# Sheet1.net
KiCad netlist of a schematic drawn in Altium Designer
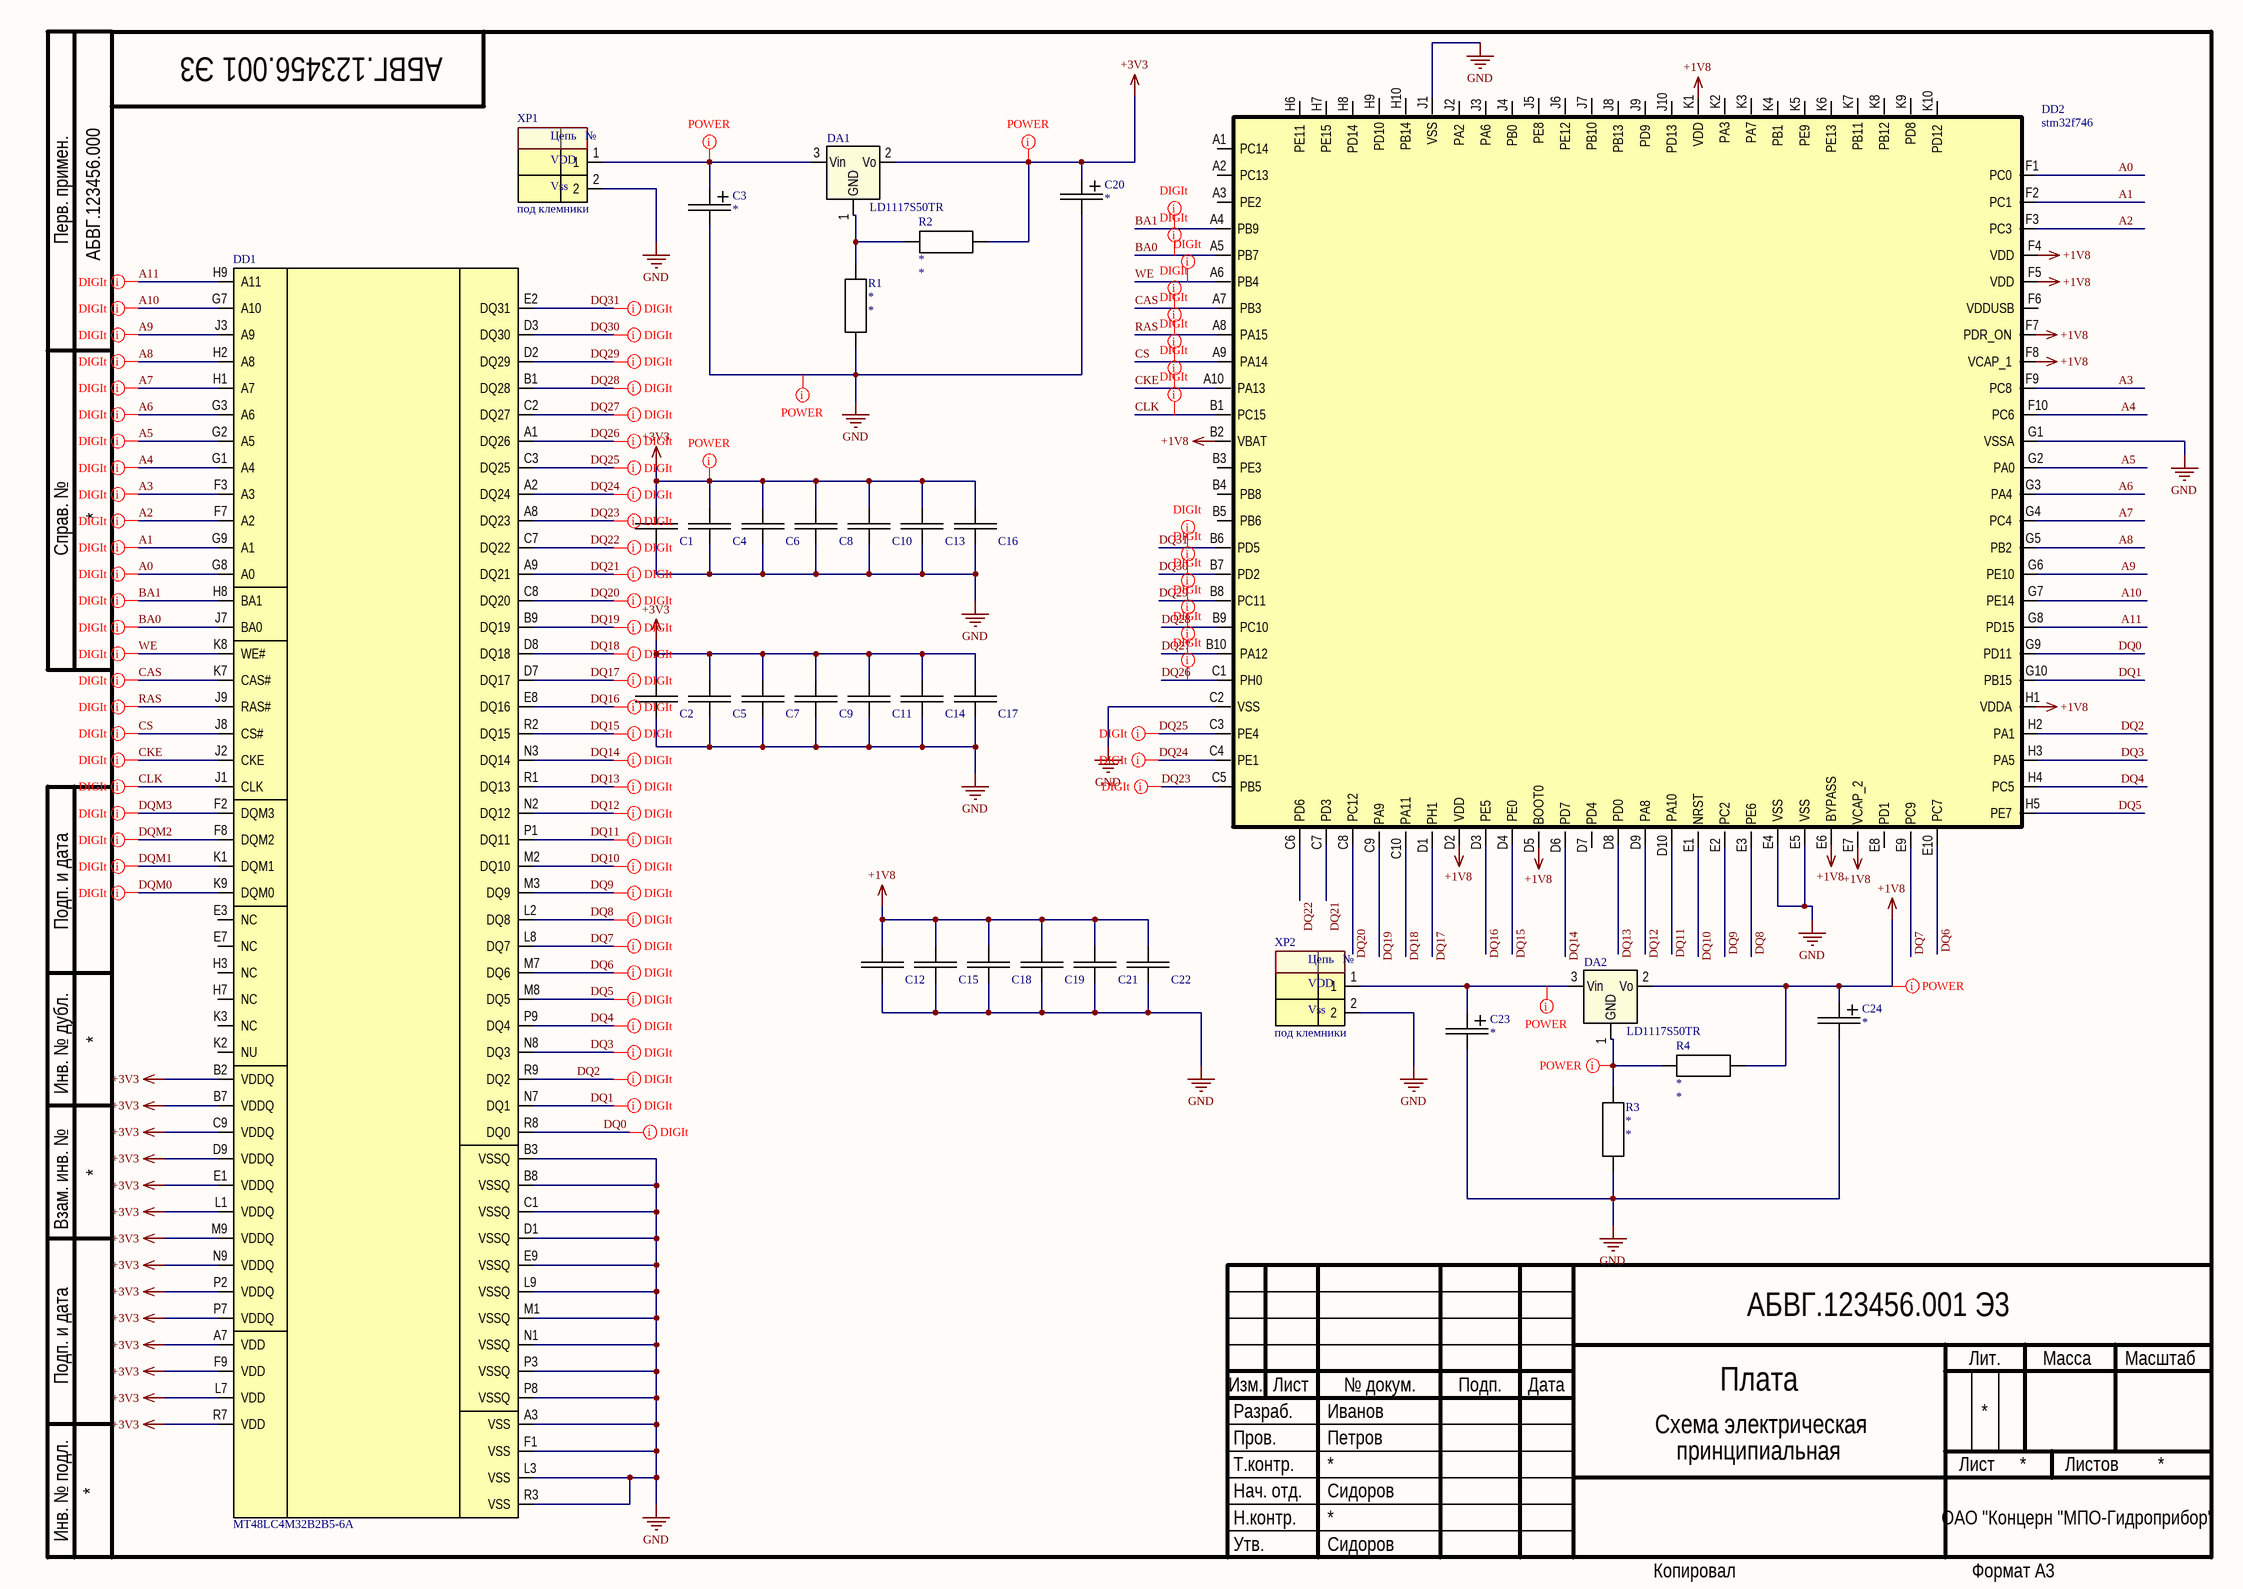
[diagram p0: Sheet1.SchDoc]

(export (version "E")
  (design (tool "Eeschema 10.0.6"))
  (components
    (comp (ref "C1") (value "*") (footprint "CAP0402_min") (libsource (lib "SchlibUGO") (part "Capasitor")))
    (comp (ref "C2") (value "*") (footprint "CAP0402_min") (libsource (lib "SchlibUGO") (part "Capasitor")))
    (comp (ref "C3")
      (value "*")
      (footprint "Capasitor Tantal TypeA MIN")
      (libsource (lib "SchlibUGO") (part "Capasitor Electrolit"))
    )
    (comp (ref "C4") (value "*") (footprint "CAP0402_min") (libsource (lib "SchlibUGO") (part "Capasitor")))
    (comp (ref "C5") (value "*") (footprint "CAP0402_min") (libsource (lib "SchlibUGO") (part "Capasitor")))
    (comp (ref "C6") (value "*") (footprint "CAP0402_min") (libsource (lib "SchlibUGO") (part "Capasitor")))
    (comp (ref "C7") (value "*") (footprint "CAP0402_min") (libsource (lib "SchlibUGO") (part "Capasitor")))
    (comp (ref "C8") (value "*") (footprint "CAP0402_min") (libsource (lib "SchlibUGO") (part "Capasitor")))
    (comp (ref "C9") (value "*") (footprint "CAP0402_min") (libsource (lib "SchlibUGO") (part "Capasitor")))
    (comp (ref "C10") (value "*") (footprint "CAP0402_min") (libsource (lib "SchlibUGO") (part "Capasitor")))
    (comp (ref "C11") (value "*") (footprint "CAP0402_min") (libsource (lib "SchlibUGO") (part "Capasitor")))
    (comp (ref "C12") (value "*") (footprint "CAP0402_min") (libsource (lib "SchlibUGO") (part "Capasitor")))
    (comp (ref "C13") (value "*") (footprint "CAP0402_min") (libsource (lib "SchlibUGO") (part "Capasitor")))
    (comp (ref "C14") (value "*") (footprint "CAP0402_min") (libsource (lib "SchlibUGO") (part "Capasitor")))
    (comp (ref "C15") (value "*") (footprint "CAP0402_min") (libsource (lib "SchlibUGO") (part "Capasitor")))
    (comp (ref "C16") (value "*") (footprint "CAP0402_min") (libsource (lib "SchlibUGO") (part "Capasitor")))
    (comp (ref "C17") (value "*") (footprint "CAP0402_min") (libsource (lib "SchlibUGO") (part "Capasitor")))
    (comp (ref "C18") (value "*") (footprint "CAP0402_min") (libsource (lib "SchlibUGO") (part "Capasitor")))
    (comp (ref "C19") (value "*") (footprint "CAP0402_min") (libsource (lib "SchlibUGO") (part "Capasitor")))
    (comp (ref "C20")
      (value "*")
      (footprint "Capasitor Tantal TypeA MIN")
      (libsource (lib "SchlibUGO") (part "Capasitor Electrolit"))
    )
    (comp (ref "C21") (value "*") (footprint "CAP0402_min") (libsource (lib "SchlibUGO") (part "Capasitor")))
    (comp (ref "C22") (value "*") (footprint "CAP0402_min") (libsource (lib "SchlibUGO") (part "Capasitor")))
    (comp (ref "C23")
      (value "*")
      (footprint "Capasitor Tantal TypeA MIN")
      (libsource (lib "SchlibUGO") (part "Capasitor Electrolit"))
    )
    (comp (ref "C24")
      (value "*")
      (footprint "Capasitor Tantal TypeA MIN")
      (libsource (lib "SchlibUGO") (part "Capasitor Electrolit"))
    )
    (comp (ref "DA1")
      (value "LD1117S50TR")
      (footprint "SOD-223")
      (fields (field (name "MANUFACTURER") "Texas Instruments"))
      (libsource (lib "SchlibUGO") (part "LD1117S50TR"))
    )
    (comp (ref "DA2")
      (value "LD1117S50TR")
      (footprint "SOD-223")
      (fields (field (name "MANUFACTURER") "Texas Instruments"))
      (libsource (lib "SchlibUGO") (part "LD1117S50TR"))
    )
    (comp (ref "DD1")
      (value "MT48LC4M32B2B5-6A")
      (footprint "VFBGA90")
      (fields (field (name "MANUFACTURER") "MICRON"))
      (libsource (lib "SchlibUGO") (part "mt48lc4m32b2b5-6a"))
    )
    (comp (ref "DD2")
      (value "stm32f746")
      (footprint "BGA100P9X9-81A")
      (fields (field (name "MANUFACTURER") "STM"))
      (libsource (lib "SchlibUGO") (part "stm32f746"))
    )
    (comp (ref "R1")
      (value "*")
      (footprint "0402")
      (fields (field (name "ALTIUM_VALUE") "*") (field (name "POWER") "*"))
      (libsource (lib "SchlibUGO") (part "Resistor"))
    )
    (comp (ref "R2")
      (value "*")
      (footprint "0402")
      (fields (field (name "ALTIUM_VALUE") "*") (field (name "POWER") "*"))
      (libsource (lib "SchlibUGO") (part "Resistor"))
    )
    (comp (ref "R3")
      (value "*")
      (footprint "0402")
      (fields (field (name "ALTIUM_VALUE") "*") (field (name "POWER") "*"))
      (libsource (lib "SchlibUGO") (part "Resistor"))
    )
    (comp (ref "R4")
      (value "*")
      (footprint "0402")
      (fields (field (name "ALTIUM_VALUE") "*") (field (name "POWER") "*"))
      (libsource (lib "SchlibUGO") (part "Resistor"))
    )
    (comp (ref "XP1")
      (value "под клемники")
      (footprint "KLS2-EDR-500-2P")
      (libsource (lib "SchlibUGO") (part "Connector_Power"))
    )
    (comp (ref "XP2")
      (value "под клемники")
      (footprint "KLS2-EDR-500-2P")
      (libsource (lib "SchlibUGO") (part "Connector_Power"))
    )
  )
  (nets
    (net (code "1") (name "+1V8") (class "Default")
      (node (ref "C12") (pin "1") (pinfunction "1_1") (pintype "passive"))
      (node (ref "C15") (pin "1") (pinfunction "1_1") (pintype "passive"))
      (node (ref "C18") (pin "1") (pinfunction "1_1") (pintype "passive"))
      (node (ref "C19") (pin "1") (pinfunction "1_1") (pintype "passive"))
      (node (ref "C21") (pin "1") (pinfunction "1_1") (pintype "passive"))
      (node (ref "C22") (pin "1") (pinfunction "1_1") (pintype "passive"))
      (node (ref "C24") (pin "1") (pinfunction "1_1") (pintype "passive"))
      (node (ref "DA2") (pin "2") (pinfunction "Vo_2") (pintype "passive"))
      (node (ref "DD2") (pin "B2") (pinfunction "VBAT_B2") (pintype "passive"))
      (node (ref "DD2") (pin "D2") (pinfunction "VDD_D2") (pintype "passive"))
      (node (ref "DD2") (pin "D5") (pinfunction "BOOT0_D5") (pintype "passive"))
      (node (ref "DD2") (pin "E6") (pinfunction "BYPASS_E6") (pintype "passive"))
      (node (ref "DD2") (pin "E7") (pinfunction "VCAP_2_E7") (pintype "passive"))
      (node (ref "DD2") (pin "F4") (pinfunction "VDD_F4") (pintype "passive"))
      (node (ref "DD2") (pin "F5") (pinfunction "VDD_F5") (pintype "passive"))
      (node (ref "DD2") (pin "F7") (pinfunction "PDR_ON_F7") (pintype "passive"))
      (node (ref "DD2") (pin "F8") (pinfunction "VCAP_1_F8") (pintype "passive"))
      (node (ref "DD2") (pin "H1") (pinfunction "VDDA_H1") (pintype "passive"))
      (node (ref "DD2") (pin "K1") (pinfunction "VDD_K1") (pintype "passive"))
      (node (ref "R4") (pin "1") (pinfunction "1_1") (pintype "passive"))
    )
    (net (code "2") (name "+3V3") (class "Default")
      (node (ref "C1") (pin "1") (pinfunction "1_1") (pintype "passive"))
      (node (ref "C10") (pin "1") (pinfunction "1_1") (pintype "passive"))
      (node (ref "C11") (pin "1") (pinfunction "1_1") (pintype "passive"))
      (node (ref "C13") (pin "1") (pinfunction "1_1") (pintype "passive"))
      (node (ref "C14") (pin "1") (pinfunction "1_1") (pintype "passive"))
      (node (ref "C16") (pin "1") (pinfunction "1_1") (pintype "passive"))
      (node (ref "C17") (pin "1") (pinfunction "1_1") (pintype "passive"))
      (node (ref "C2") (pin "1") (pinfunction "1_1") (pintype "passive"))
      (node (ref "C20") (pin "1") (pinfunction "1_1") (pintype "passive"))
      (node (ref "C4") (pin "1") (pinfunction "1_1") (pintype "passive"))
      (node (ref "C5") (pin "1") (pinfunction "1_1") (pintype "passive"))
      (node (ref "C6") (pin "1") (pinfunction "1_1") (pintype "passive"))
      (node (ref "C7") (pin "1") (pinfunction "1_1") (pintype "passive"))
      (node (ref "C8") (pin "1") (pinfunction "1_1") (pintype "passive"))
      (node (ref "C9") (pin "1") (pinfunction "1_1") (pintype "passive"))
      (node (ref "DA1") (pin "2") (pinfunction "Vo_2") (pintype "passive"))
      (node (ref "DD1") (pin "A7") (pinfunction "VDD_A7") (pintype "passive"))
      (node (ref "DD1") (pin "B2") (pinfunction "VDDQ_B2") (pintype "passive"))
      (node (ref "DD1") (pin "B7") (pinfunction "VDDQ_B7") (pintype "passive"))
      (node (ref "DD1") (pin "C9") (pinfunction "VDDQ_C9") (pintype "passive"))
      (node (ref "DD1") (pin "D9") (pinfunction "VDDQ_D9") (pintype "passive"))
      (node (ref "DD1") (pin "E1") (pinfunction "VDDQ_E1") (pintype "passive"))
      (node (ref "DD1") (pin "F9") (pinfunction "VDD_F9") (pintype "passive"))
      (node (ref "DD1") (pin "L1") (pinfunction "VDDQ_L1") (pintype "passive"))
      (node (ref "DD1") (pin "L7") (pinfunction "VDD_L7") (pintype "passive"))
      (node (ref "DD1") (pin "M9") (pinfunction "VDDQ_M9") (pintype "passive"))
      (node (ref "DD1") (pin "N9") (pinfunction "VDDQ_N9") (pintype "passive"))
      (node (ref "DD1") (pin "P2") (pinfunction "VDDQ_P2") (pintype "passive"))
      (node (ref "DD1") (pin "P7") (pinfunction "VDDQ_P7") (pintype "passive"))
      (node (ref "DD1") (pin "R7") (pinfunction "VDD_R7") (pintype "passive"))
      (node (ref "R2") (pin "1") (pinfunction "1_1") (pintype "passive"))
    )
    (net (code "3") (name "/A0") (class "Default")
      (node (ref "DD1") (pin "G8") (pinfunction "A0_G8") (pintype "passive"))
      (node (ref "DD2") (pin "F1") (pinfunction "PC0_F1") (pintype "passive"))
    )
    (net (code "4") (name "/A1") (class "Default")
      (node (ref "DD1") (pin "G9") (pinfunction "A1_G9") (pintype "passive"))
      (node (ref "DD2") (pin "F2") (pinfunction "PC1_F2") (pintype "passive"))
    )
    (net (code "5") (name "/A2") (class "Default")
      (node (ref "DD1") (pin "F7") (pinfunction "A2_F7") (pintype "passive"))
      (node (ref "DD2") (pin "F3") (pinfunction "PC3_F3") (pintype "passive"))
    )
    (net (code "6") (name "/A3") (class "Default")
      (node (ref "DD1") (pin "F3") (pinfunction "A3_F3") (pintype "passive"))
      (node (ref "DD2") (pin "F9") (pinfunction "PC8_F9") (pintype "passive"))
    )
    (net (code "7") (name "/A4") (class "Default")
      (node (ref "DD1") (pin "G1") (pinfunction "A4_G1") (pintype "passive"))
      (node (ref "DD2") (pin "F10") (pinfunction "PC6_F10") (pintype "passive"))
    )
    (net (code "8") (name "/A5") (class "Default")
      (node (ref "DD1") (pin "G2") (pinfunction "A5_G2") (pintype "passive"))
      (node (ref "DD2") (pin "G2") (pinfunction "PA0_G2") (pintype "passive"))
    )
    (net (code "9") (name "/A6") (class "Default")
      (node (ref "DD1") (pin "G3") (pinfunction "A6_G3") (pintype "passive"))
      (node (ref "DD2") (pin "G3") (pinfunction "PA4_G3") (pintype "passive"))
    )
    (net (code "10") (name "/A7") (class "Default")
      (node (ref "DD1") (pin "H1") (pinfunction "A7_H1") (pintype "passive"))
      (node (ref "DD2") (pin "G4") (pinfunction "PC4_G4") (pintype "passive"))
    )
    (net (code "11") (name "/A8") (class "Default")
      (node (ref "DD1") (pin "H2") (pinfunction "A8_H2") (pintype "passive"))
      (node (ref "DD2") (pin "G5") (pinfunction "PB2_G5") (pintype "passive"))
    )
    (net (code "12") (name "/A9") (class "Default")
      (node (ref "DD1") (pin "J3") (pinfunction "A9_J3") (pintype "passive"))
      (node (ref "DD2") (pin "G6") (pinfunction "PE10_G6") (pintype "passive"))
    )
    (net (code "13") (name "/A10") (class "Default")
      (node (ref "DD1") (pin "G7") (pinfunction "A10_G7") (pintype "passive"))
      (node (ref "DD2") (pin "G7") (pinfunction "PE14_G7") (pintype "passive"))
    )
    (net (code "14") (name "/A11") (class "Default")
      (node (ref "DD1") (pin "H9") (pinfunction "A11_H9") (pintype "passive"))
      (node (ref "DD2") (pin "G8") (pinfunction "PD15_G8") (pintype "passive"))
    )
    (net (code "15") (name "/BA0") (class "Default")
      (node (ref "DD1") (pin "J7") (pinfunction "BA0_J7") (pintype "passive"))
      (node (ref "DD2") (pin "A5") (pinfunction "PB7_A5") (pintype "passive"))
    )
    (net (code "16") (name "/BA1") (class "Default")
      (node (ref "DD1") (pin "H8") (pinfunction "BA1_H8") (pintype "passive"))
      (node (ref "DD2") (pin "A4") (pinfunction "PB9_A4") (pintype "passive"))
    )
    (net (code "17") (name "/CAS") (class "Default")
      (node (ref "DD1") (pin "K7") (pinfunction "CAS#_K7") (pintype "passive"))
      (node (ref "DD2") (pin "A7") (pinfunction "PB3_A7") (pintype "passive"))
    )
    (net (code "18") (name "/CKE") (class "Default")
      (node (ref "DD1") (pin "J2") (pinfunction "CKE_J2") (pintype "passive"))
      (node (ref "DD2") (pin "A10") (pinfunction "PA13_A10") (pintype "passive"))
    )
    (net (code "19") (name "/CLK") (class "Default")
      (node (ref "DD1") (pin "J1") (pinfunction "CLK_J1") (pintype "passive"))
      (node (ref "DD2") (pin "B1") (pinfunction "PC15_B1") (pintype "passive"))
    )
    (net (code "20") (name "/CS") (class "Default")
      (node (ref "DD1") (pin "J8") (pinfunction "CS#_J8") (pintype "passive"))
      (node (ref "DD2") (pin "A9") (pinfunction "PA14_A9") (pintype "passive"))
    )
    (net (code "21") (name "/DQ0") (class "Default")
      (node (ref "DD1") (pin "R8") (pinfunction "DQ0_R8") (pintype "passive"))
      (node (ref "DD2") (pin "G9") (pinfunction "PD11_G9") (pintype "passive"))
    )
    (net (code "22") (name "/DQ1") (class "Default")
      (node (ref "DD1") (pin "N7") (pinfunction "DQ1_N7") (pintype "passive"))
      (node (ref "DD2") (pin "G10") (pinfunction "PB15_G10") (pintype "passive"))
    )
    (net (code "23") (name "/DQ2") (class "Default")
      (node (ref "DD1") (pin "R9") (pinfunction "DQ2_R9") (pintype "passive"))
      (node (ref "DD2") (pin "H2") (pinfunction "PA1_H2") (pintype "passive"))
    )
    (net (code "24") (name "/DQ3") (class "Default")
      (node (ref "DD1") (pin "N8") (pinfunction "DQ3_N8") (pintype "passive"))
      (node (ref "DD2") (pin "H3") (pinfunction "PA5_H3") (pintype "passive"))
    )
    (net (code "25") (name "/DQ4") (class "Default")
      (node (ref "DD1") (pin "P9") (pinfunction "DQ4_P9") (pintype "passive"))
      (node (ref "DD2") (pin "H4") (pinfunction "PC5_H4") (pintype "passive"))
    )
    (net (code "26") (name "/DQ5") (class "Default")
      (node (ref "DD1") (pin "M8") (pinfunction "DQ5_M8") (pintype "passive"))
      (node (ref "DD2") (pin "H5") (pinfunction "PE7_H5") (pintype "passive"))
    )
    (net (code "27") (name "/DQ6") (class "Default")
      (node (ref "DD1") (pin "M7") (pinfunction "DQ6_M7") (pintype "passive"))
      (node (ref "DD2") (pin "E10") (pinfunction "PC7_E10") (pintype "passive"))
    )
    (net (code "28") (name "/DQ7") (class "Default")
      (node (ref "DD1") (pin "L8") (pinfunction "DQ7_L8") (pintype "passive"))
      (node (ref "DD2") (pin "E9") (pinfunction "PC9_E9") (pintype "passive"))
    )
    (net (code "29") (name "/DQ8") (class "Default")
      (node (ref "DD1") (pin "L2") (pinfunction "DQ8_L2") (pintype "passive"))
      (node (ref "DD2") (pin "E3") (pinfunction "PE6_E3") (pintype "passive"))
    )
    (net (code "30") (name "/DQ9") (class "Default")
      (node (ref "DD1") (pin "M3") (pinfunction "DQ9_M3") (pintype "passive"))
      (node (ref "DD2") (pin "E2") (pinfunction "PC2_E2") (pintype "passive"))
    )
    (net (code "31") (name "/DQ10") (class "Default")
      (node (ref "DD1") (pin "M2") (pinfunction "DQ10_M2") (pintype "passive"))
      (node (ref "DD2") (pin "E1") (pinfunction "NRST_E1") (pintype "passive"))
    )
    (net (code "32") (name "/DQ11") (class "Default")
      (node (ref "DD1") (pin "P1") (pinfunction "DQ11_P1") (pintype "passive"))
      (node (ref "DD2") (pin "D10") (pinfunction "PA10_D10") (pintype "passive"))
    )
    (net (code "33") (name "/DQ12") (class "Default")
      (node (ref "DD1") (pin "N2") (pinfunction "DQ12_N2") (pintype "passive"))
      (node (ref "DD2") (pin "D9") (pinfunction "PA8_D9") (pintype "passive"))
    )
    (net (code "34") (name "/DQ13") (class "Default")
      (node (ref "DD1") (pin "R1") (pinfunction "DQ13_R1") (pintype "passive"))
      (node (ref "DD2") (pin "D8") (pinfunction "PD0_D8") (pintype "passive"))
    )
    (net (code "35") (name "/DQ14") (class "Default")
      (node (ref "DD1") (pin "N3") (pinfunction "DQ14_N3") (pintype "passive"))
      (node (ref "DD2") (pin "D6") (pinfunction "PD7_D6") (pintype "passive"))
    )
    (net (code "36") (name "/DQ15") (class "Default")
      (node (ref "DD1") (pin "R2") (pinfunction "DQ15_R2") (pintype "passive"))
      (node (ref "DD2") (pin "D4") (pinfunction "PE0_D4") (pintype "passive"))
    )
    (net (code "37") (name "/DQ16") (class "Default")
      (node (ref "DD1") (pin "E8") (pinfunction "DQ16_E8") (pintype "passive"))
      (node (ref "DD2") (pin "D3") (pinfunction "PE5_D3") (pintype "passive"))
    )
    (net (code "38") (name "/DQ17") (class "Default")
      (node (ref "DD1") (pin "D7") (pinfunction "DQ17_D7") (pintype "passive"))
      (node (ref "DD2") (pin "D1") (pinfunction "PH1_D1") (pintype "passive"))
    )
    (net (code "39") (name "/DQ18") (class "Default")
      (node (ref "DD1") (pin "D8") (pinfunction "DQ18_D8") (pintype "passive"))
      (node (ref "DD2") (pin "C10") (pinfunction "PA11_C10") (pintype "passive"))
    )
    (net (code "40") (name "/DQ19") (class "Default")
      (node (ref "DD1") (pin "B9") (pinfunction "DQ19_B9") (pintype "passive"))
      (node (ref "DD2") (pin "C9") (pinfunction "PA9_C9") (pintype "passive"))
    )
    (net (code "41") (name "/DQ20") (class "Default")
      (node (ref "DD1") (pin "C8") (pinfunction "DQ20_C8") (pintype "passive"))
      (node (ref "DD2") (pin "C8") (pinfunction "PC12_C8") (pintype "passive"))
    )
    (net (code "42") (name "/DQ21") (class "Default")
      (node (ref "DD1") (pin "A9") (pinfunction "DQ21_A9") (pintype "passive"))
      (node (ref "DD2") (pin "C7") (pinfunction "PD3_C7") (pintype "passive"))
    )
    (net (code "43") (name "/DQ22") (class "Default")
      (node (ref "DD1") (pin "C7") (pinfunction "DQ22_C7") (pintype "passive"))
      (node (ref "DD2") (pin "C6") (pinfunction "PD6_C6") (pintype "passive"))
    )
    (net (code "44") (name "/DQ23") (class "Default")
      (node (ref "DD1") (pin "A8") (pinfunction "DQ23_A8") (pintype "passive"))
      (node (ref "DD2") (pin "C5") (pinfunction "PB5_C5") (pintype "passive"))
    )
    (net (code "45") (name "/DQ24") (class "Default")
      (node (ref "DD1") (pin "A2") (pinfunction "DQ24_A2") (pintype "passive"))
      (node (ref "DD2") (pin "C4") (pinfunction "PE1_C4") (pintype "passive"))
    )
    (net (code "46") (name "/DQ25") (class "Default")
      (node (ref "DD1") (pin "C3") (pinfunction "DQ25_C3") (pintype "passive"))
      (node (ref "DD2") (pin "C3") (pinfunction "PE4_C3") (pintype "passive"))
    )
    (net (code "47") (name "/DQ26") (class "Default")
      (node (ref "DD1") (pin "A1") (pinfunction "DQ26_A1") (pintype "passive"))
      (node (ref "DD2") (pin "C1") (pinfunction "PH0_C1") (pintype "passive"))
    )
    (net (code "48") (name "/DQ27") (class "Default")
      (node (ref "DD1") (pin "C2") (pinfunction "DQ27_C2") (pintype "passive"))
      (node (ref "DD2") (pin "B10") (pinfunction "PA12_B10") (pintype "passive"))
    )
    (net (code "49") (name "/DQ28") (class "Default")
      (node (ref "DD1") (pin "B1") (pinfunction "DQ28_B1") (pintype "passive"))
      (node (ref "DD2") (pin "B9") (pinfunction "PC10_B9") (pintype "passive"))
    )
    (net (code "50") (name "/DQ29") (class "Default")
      (node (ref "DD1") (pin "D2") (pinfunction "DQ29_D2") (pintype "passive"))
      (node (ref "DD2") (pin "B8") (pinfunction "PC11_B8") (pintype "passive"))
    )
    (net (code "51") (name "/DQ30") (class "Default")
      (node (ref "DD1") (pin "D3") (pinfunction "DQ30_D3") (pintype "passive"))
      (node (ref "DD2") (pin "B7") (pinfunction "PD2_B7") (pintype "passive"))
    )
    (net (code "52") (name "/DQ31") (class "Default")
      (node (ref "DD1") (pin "E2") (pinfunction "DQ31_E2") (pintype "passive"))
      (node (ref "DD2") (pin "B6") (pinfunction "PD5_B6") (pintype "passive"))
    )
    (net (code "53") (name "/DQM0") (class "Default")
      (node (ref "DD1") (pin "K9") (pinfunction "DQM0_K9") (pintype "passive"))
    )
    (net (code "54") (name "/DQM1") (class "Default")
      (node (ref "DD1") (pin "K1") (pinfunction "DQM1_K1") (pintype "passive"))
    )
    (net (code "55") (name "/DQM2") (class "Default")
      (node (ref "DD1") (pin "F8") (pinfunction "DQM2_F8") (pintype "passive"))
    )
    (net (code "56") (name "/DQM3") (class "Default")
      (node (ref "DD1") (pin "F2") (pinfunction "DQM3_F2") (pintype "passive"))
    )
    (net (code "57") (name "/RAS") (class "Default")
      (node (ref "DD1") (pin "J9") (pinfunction "RAS#_J9") (pintype "passive"))
      (node (ref "DD2") (pin "A8") (pinfunction "PA15_A8") (pintype "passive"))
    )
    (net (code "58") (name "/WE") (class "Default")
      (node (ref "DD1") (pin "K8") (pinfunction "WE#_K8") (pintype "passive"))
      (node (ref "DD2") (pin "A6") (pinfunction "PB4_A6") (pintype "passive"))
    )
    (net (code "59") (name "GND") (class "Default")
      (node (ref "C1") (pin "2") (pinfunction "2_2") (pintype "passive"))
      (node (ref "C10") (pin "2") (pinfunction "2_2") (pintype "passive"))
      (node (ref "C11") (pin "2") (pinfunction "2_2") (pintype "passive"))
      (node (ref "C12") (pin "2") (pinfunction "2_2") (pintype "passive"))
      (node (ref "C13") (pin "2") (pinfunction "2_2") (pintype "passive"))
      (node (ref "C14") (pin "2") (pinfunction "2_2") (pintype "passive"))
      (node (ref "C15") (pin "2") (pinfunction "2_2") (pintype "passive"))
      (node (ref "C16") (pin "2") (pinfunction "2_2") (pintype "passive"))
      (node (ref "C17") (pin "2") (pinfunction "2_2") (pintype "passive"))
      (node (ref "C18") (pin "2") (pinfunction "2_2") (pintype "passive"))
      (node (ref "C19") (pin "2") (pinfunction "2_2") (pintype "passive"))
      (node (ref "C2") (pin "2") (pinfunction "2_2") (pintype "passive"))
      (node (ref "C20") (pin "2") (pinfunction "2_2") (pintype "passive"))
      (node (ref "C21") (pin "2") (pinfunction "2_2") (pintype "passive"))
      (node (ref "C22") (pin "2") (pinfunction "2_2") (pintype "passive"))
      (node (ref "C23") (pin "2") (pinfunction "2_2") (pintype "passive"))
      (node (ref "C24") (pin "2") (pinfunction "2_2") (pintype "passive"))
      (node (ref "C3") (pin "2") (pinfunction "2_2") (pintype "passive"))
      (node (ref "C4") (pin "2") (pinfunction "2_2") (pintype "passive"))
      (node (ref "C5") (pin "2") (pinfunction "2_2") (pintype "passive"))
      (node (ref "C6") (pin "2") (pinfunction "2_2") (pintype "passive"))
      (node (ref "C7") (pin "2") (pinfunction "2_2") (pintype "passive"))
      (node (ref "C8") (pin "2") (pinfunction "2_2") (pintype "passive"))
      (node (ref "C9") (pin "2") (pinfunction "2_2") (pintype "passive"))
      (node (ref "DD1") (pin "A3") (pinfunction "VSS_A3") (pintype "passive"))
      (node (ref "DD1") (pin "B3") (pinfunction "VSSQ_B3") (pintype "passive"))
      (node (ref "DD1") (pin "B8") (pinfunction "VSSQ_B8") (pintype "passive"))
      (node (ref "DD1") (pin "C1") (pinfunction "VSSQ_C1") (pintype "passive"))
      (node (ref "DD1") (pin "D1") (pinfunction "VSSQ_D1") (pintype "passive"))
      (node (ref "DD1") (pin "E9") (pinfunction "VSSQ_E9") (pintype "passive"))
      (node (ref "DD1") (pin "F1") (pinfunction "VSS_F1") (pintype "passive"))
      (node (ref "DD1") (pin "L3") (pinfunction "VSS_L3") (pintype "passive"))
      (node (ref "DD1") (pin "L9") (pinfunction "VSSQ_L9") (pintype "passive"))
      (node (ref "DD1") (pin "M1") (pinfunction "VSSQ_M1") (pintype "passive"))
      (node (ref "DD1") (pin "N1") (pinfunction "VSSQ_N1") (pintype "passive"))
      (node (ref "DD1") (pin "P3") (pinfunction "VSSQ_P3") (pintype "passive"))
      (node (ref "DD1") (pin "P8") (pinfunction "VSSQ_P8") (pintype "passive"))
      (node (ref "DD1") (pin "R3") (pinfunction "VSS_R3") (pintype "passive"))
      (node (ref "DD2") (pin "C2") (pinfunction "VSS_C2") (pintype "passive"))
      (node (ref "DD2") (pin "E4") (pinfunction "VSS_E4") (pintype "passive"))
      (node (ref "DD2") (pin "E5") (pinfunction "VSS_E5") (pintype "passive"))
      (node (ref "DD2") (pin "G1") (pinfunction "VSSA_G1") (pintype "passive"))
      (node (ref "DD2") (pin "J1") (pinfunction "VSS_J1") (pintype "passive"))
      (node (ref "R1") (pin "1") (pinfunction "1_1") (pintype "passive"))
      (node (ref "R3") (pin "1") (pinfunction "1_1") (pintype "passive"))
      (node (ref "XP1") (pin "2") (pinfunction "2_2") (pintype "passive"))
      (node (ref "XP2") (pin "2") (pinfunction "2_2") (pintype "passive"))
    )
    (net (code "60") (name "Net-(DA1-GND)") (class "Default")
      (node (ref "DA1") (pin "1") (pinfunction "GND_1") (pintype "passive"))
      (node (ref "R1") (pin "2") (pinfunction "2_2") (pintype "passive"))
      (node (ref "R2") (pin "2") (pinfunction "2_2") (pintype "passive"))
    )
    (net (code "61") (name "Net-(DA1-Vin)") (class "Default")
      (node (ref "C3") (pin "1") (pinfunction "1_1") (pintype "passive"))
      (node (ref "DA1") (pin "3") (pinfunction "Vin_3") (pintype "passive"))
      (node (ref "XP1") (pin "1") (pinfunction "1_1") (pintype "passive"))
    )
    (net (code "62") (name "Net-(DA2-GND)") (class "Default")
      (node (ref "DA2") (pin "1") (pinfunction "GND_1") (pintype "passive"))
      (node (ref "R3") (pin "2") (pinfunction "2_2") (pintype "passive"))
      (node (ref "R4") (pin "2") (pinfunction "2_2") (pintype "passive"))
    )
    (net (code "63") (name "Net-(DA2-Vin)") (class "Default")
      (node (ref "C23") (pin "1") (pinfunction "1_1") (pintype "passive"))
      (node (ref "DA2") (pin "3") (pinfunction "Vin_3") (pintype "passive"))
      (node (ref "XP2") (pin "1") (pinfunction "1_1") (pintype "passive"))
    )
    (net (code "64") (name "unconnected-(DD1-NC-PadE3)") (class "Default")
      (node (ref "DD1") (pin "E3") (pinfunction "NC_E3") (pintype "passive"))
    )
    (net (code "65") (name "unconnected-(DD1-NC-PadE7)") (class "Default")
      (node (ref "DD1") (pin "E7") (pinfunction "NC_E7") (pintype "passive"))
    )
    (net (code "66") (name "unconnected-(DD1-NC-PadH3)") (class "Default")
      (node (ref "DD1") (pin "H3") (pinfunction "NC_H3") (pintype "passive"))
    )
    (net (code "67") (name "unconnected-(DD1-NC-PadH7)") (class "Default")
      (node (ref "DD1") (pin "H7") (pinfunction "NC_H7") (pintype "passive"))
    )
    (net (code "68") (name "unconnected-(DD1-NC-PadK3)") (class "Default")
      (node (ref "DD1") (pin "K3") (pinfunction "NC_K3") (pintype "passive"))
    )
    (net (code "69") (name "unconnected-(DD1-NU-PadK2)") (class "Default")
      (node (ref "DD1") (pin "K2") (pinfunction "NU_K2") (pintype "passive"))
    )
    (net (code "70") (name "unconnected-(DD2-PA2-PadJ2)") (class "Default")
      (node (ref "DD2") (pin "J2") (pinfunction "PA2_J2") (pintype "passive"))
    )
    (net (code "71") (name "unconnected-(DD2-PA3-PadK2)") (class "Default")
      (node (ref "DD2") (pin "K2") (pinfunction "PA3_K2") (pintype "passive"))
    )
    (net (code "72") (name "unconnected-(DD2-PA6-PadJ3)") (class "Default")
      (node (ref "DD2") (pin "J3") (pinfunction "PA6_J3") (pintype "passive"))
    )
    (net (code "73") (name "unconnected-(DD2-PA7-PadK3)") (class "Default")
      (node (ref "DD2") (pin "K3") (pinfunction "PA7_K3") (pintype "passive"))
    )
    (net (code "74") (name "unconnected-(DD2-PB0-PadJ4)") (class "Default")
      (node (ref "DD2") (pin "J4") (pinfunction "PB0_J4") (pintype "passive"))
    )
    (net (code "75") (name "unconnected-(DD2-PB1-PadK4)") (class "Default")
      (node (ref "DD2") (pin "K4") (pinfunction "PB1_K4") (pintype "passive"))
    )
    (net (code "76") (name "unconnected-(DD2-PB6-PadB5)") (class "Default")
      (node (ref "DD2") (pin "B5") (pinfunction "PB6_B5") (pintype "passive"))
    )
    (net (code "77") (name "unconnected-(DD2-PB8-PadB4)") (class "Default")
      (node (ref "DD2") (pin "B4") (pinfunction "PB8_B4") (pintype "passive"))
    )
    (net (code "78") (name "unconnected-(DD2-PB10-PadJ7)") (class "Default")
      (node (ref "DD2") (pin "J7") (pinfunction "PB10_J7") (pintype "passive"))
    )
    (net (code "79") (name "unconnected-(DD2-PB11-PadK7)") (class "Default")
      (node (ref "DD2") (pin "K7") (pinfunction "PB11_K7") (pintype "passive"))
    )
    (net (code "80") (name "unconnected-(DD2-PB12-PadK8)") (class "Default")
      (node (ref "DD2") (pin "K8") (pinfunction "PB12_K8") (pintype "passive"))
    )
    (net (code "81") (name "unconnected-(DD2-PB13-PadJ8)") (class "Default")
      (node (ref "DD2") (pin "J8") (pinfunction "PB13_J8") (pintype "passive"))
    )
    (net (code "82") (name "unconnected-(DD2-PB14-PadH10)") (class "Default")
      (node (ref "DD2") (pin "H10") (pinfunction "PB14_H10") (pintype "passive"))
    )
    (net (code "83") (name "unconnected-(DD2-PC13-PadA2)") (class "Default")
      (node (ref "DD2") (pin "A2") (pinfunction "PC13_A2") (pintype "passive"))
    )
    (net (code "84") (name "unconnected-(DD2-PC14-PadA1)") (class "Default")
      (node (ref "DD2") (pin "A1") (pinfunction "PC14_A1") (pintype "passive"))
    )
    (net (code "85") (name "unconnected-(DD2-PD1-PadE8)") (class "Default")
      (node (ref "DD2") (pin "E8") (pinfunction "PD1_E8") (pintype "passive"))
    )
    (net (code "86") (name "unconnected-(DD2-PD4-PadD7)") (class "Default")
      (node (ref "DD2") (pin "D7") (pinfunction "PD4_D7") (pintype "passive"))
    )
    (net (code "87") (name "unconnected-(DD2-PD8-PadK9)") (class "Default")
      (node (ref "DD2") (pin "K9") (pinfunction "PD8_K9") (pintype "passive"))
    )
    (net (code "88") (name "unconnected-(DD2-PD9-PadJ9)") (class "Default")
      (node (ref "DD2") (pin "J9") (pinfunction "PD9_J9") (pintype "passive"))
    )
    (net (code "89") (name "unconnected-(DD2-PD10-PadH9)") (class "Default")
      (node (ref "DD2") (pin "H9") (pinfunction "PD10_H9") (pintype "passive"))
    )
    (net (code "90") (name "unconnected-(DD2-PD12-PadK10)") (class "Default")
      (node (ref "DD2") (pin "K10") (pinfunction "PD12_K10") (pintype "passive"))
    )
    (net (code "91") (name "unconnected-(DD2-PD13-PadJ10)") (class "Default")
      (node (ref "DD2") (pin "J10") (pinfunction "PD13_J10") (pintype "passive"))
    )
    (net (code "92") (name "unconnected-(DD2-PD14-PadH8)") (class "Default")
      (node (ref "DD2") (pin "H8") (pinfunction "PD14_H8") (pintype "passive"))
    )
    (net (code "93") (name "unconnected-(DD2-PE2-PadA3)") (class "Default")
      (node (ref "DD2") (pin "A3") (pinfunction "PE2_A3") (pintype "passive"))
    )
    (net (code "94") (name "unconnected-(DD2-PE3-PadB3)") (class "Default")
      (node (ref "DD2") (pin "B3") (pinfunction "PE3_B3") (pintype "passive"))
    )
    (net (code "95") (name "unconnected-(DD2-PE8-PadJ5)") (class "Default")
      (node (ref "DD2") (pin "J5") (pinfunction "PE8_J5") (pintype "passive"))
    )
    (net (code "96") (name "unconnected-(DD2-PE9-PadK5)") (class "Default")
      (node (ref "DD2") (pin "K5") (pinfunction "PE9_K5") (pintype "passive"))
    )
    (net (code "97") (name "unconnected-(DD2-PE11-PadH6)") (class "Default")
      (node (ref "DD2") (pin "H6") (pinfunction "PE11_H6") (pintype "passive"))
    )
    (net (code "98") (name "unconnected-(DD2-PE12-PadJ6)") (class "Default")
      (node (ref "DD2") (pin "J6") (pinfunction "PE12_J6") (pintype "passive"))
    )
    (net (code "99") (name "unconnected-(DD2-PE13-PadK6)") (class "Default")
      (node (ref "DD2") (pin "K6") (pinfunction "PE13_K6") (pintype "passive"))
    )
    (net (code "100") (name "unconnected-(DD2-PE15-PadH7)") (class "Default")
      (node (ref "DD2") (pin "H7") (pinfunction "PE15_H7") (pintype "passive"))
    )
    (net (code "101") (name "unconnected-(DD2-VDDUSB-PadF6)") (class "Default")
      (node (ref "DD2") (pin "F6") (pinfunction "VDDUSB_F6") (pintype "passive"))
    )
  )
)
